# pca9554d-3.net
KiCad netlist of a schematic drawn in EAGLE
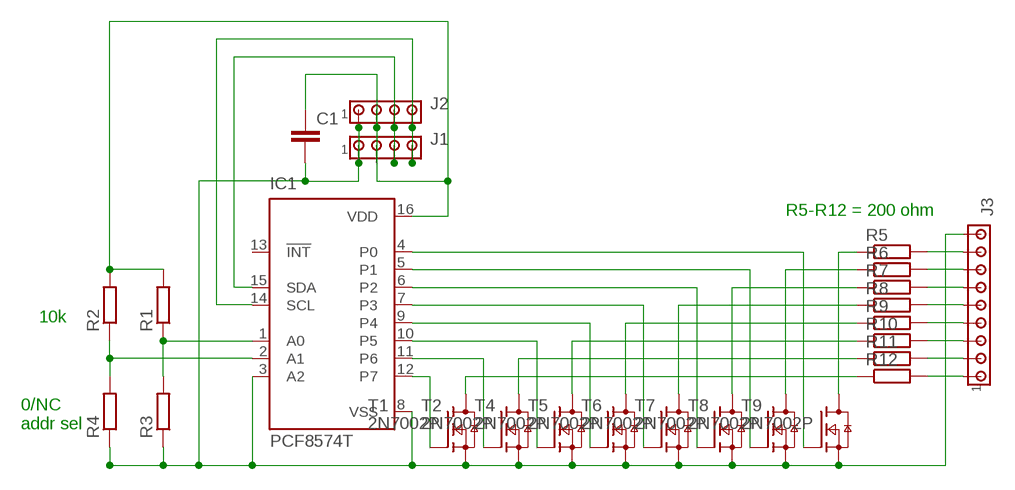
[diagram p0: schematic, sheet 1]

(export (version "E")
  (design (tool "Eeschema 10.0.6"))
  (components
    (comp (ref "C1")
      (value "C-EUC1206")
      (footprint "eagle-import:C1206")
      (libsource (lib "eagle-import") (part "C-EUC1206"))
    )
    (comp (ref "IC1")
      (value "PCF8574T")
      (footprint "eagle-import:SO16W")
      (fields (field (name "MPN") "PCF8574T/3,512"))
      (libsource (lib "eagle-import") (part "PCF8574T"))
    )
    (comp (ref "J1")
      (value "MTA04-100")
      (footprint "eagle-import:10X04MTA")
      (libsource (lib "eagle-import") (part "MTA04-100"))
    )
    (comp (ref "J2")
      (value "MTA04-100")
      (footprint "eagle-import:10X04MTA")
      (libsource (lib "eagle-import") (part "MTA04-100"))
    )
    (comp (ref "J3")
      (value "MTA09-100")
      (footprint "eagle-import:10X09MTA")
      (libsource (lib "eagle-import") (part "MTA09-100"))
    )
    (comp (ref "R1")
      (value "R-EU_R0805")
      (footprint "eagle-import:R0805")
      (libsource (lib "eagle-import") (part "resistor_R-EU_R0805"))
    )
    (comp (ref "R2")
      (value "R-EU_R0805")
      (footprint "eagle-import:R0805")
      (libsource (lib "eagle-import") (part "resistor_R-EU_R0805"))
    )
    (comp (ref "R3")
      (value "R-EU_R0402")
      (footprint "eagle-import:R0402")
      (libsource (lib "eagle-import") (part "R-EU_R0402"))
    )
    (comp (ref "R4")
      (value "R-EU_R0402")
      (footprint "eagle-import:R0402")
      (libsource (lib "eagle-import") (part "R-EU_R0402"))
    )
    (comp (ref "R5")
      (value "R-EU_R0805W")
      (footprint "eagle-import:R0805W")
      (libsource (lib "eagle-import") (part "resistor_R-EU_R0805W"))
    )
    (comp (ref "R6")
      (value "R-EU_R0805W")
      (footprint "eagle-import:R0805W")
      (libsource (lib "eagle-import") (part "resistor_R-EU_R0805W"))
    )
    (comp (ref "R7")
      (value "R-EU_R0805W")
      (footprint "eagle-import:R0805W")
      (libsource (lib "eagle-import") (part "resistor_R-EU_R0805W"))
    )
    (comp (ref "R8")
      (value "R-EU_R0805W")
      (footprint "eagle-import:R0805W")
      (libsource (lib "eagle-import") (part "resistor_R-EU_R0805W"))
    )
    (comp (ref "R9")
      (value "R-EU_R0805W")
      (footprint "eagle-import:R0805W")
      (libsource (lib "eagle-import") (part "resistor_R-EU_R0805W"))
    )
    (comp (ref "R10")
      (value "R-EU_R0805W")
      (footprint "eagle-import:R0805W")
      (libsource (lib "eagle-import") (part "resistor_R-EU_R0805W"))
    )
    (comp (ref "R11")
      (value "R-EU_R0805W")
      (footprint "eagle-import:R0805W")
      (libsource (lib "eagle-import") (part "resistor_R-EU_R0805W"))
    )
    (comp (ref "R12")
      (value "R-EU_R0805W")
      (footprint "eagle-import:R0805W")
      (libsource (lib "eagle-import") (part "resistor_R-EU_R0805W"))
    )
    (comp (ref "T1")
      (value "2N7002P")
      (footprint "eagle-import:SOT23")
      (libsource (lib "eagle-import") (part "2N7002P"))
    )
    (comp (ref "T2")
      (value "2N7002P")
      (footprint "eagle-import:SOT23")
      (libsource (lib "eagle-import") (part "2N7002P"))
    )
    (comp (ref "T4")
      (value "2N7002P")
      (footprint "eagle-import:SOT23")
      (libsource (lib "eagle-import") (part "2N7002P"))
    )
    (comp (ref "T5")
      (value "2N7002P")
      (footprint "eagle-import:SOT23")
      (libsource (lib "eagle-import") (part "2N7002P"))
    )
    (comp (ref "T6")
      (value "2N7002P")
      (footprint "eagle-import:SOT23")
      (libsource (lib "eagle-import") (part "2N7002P"))
    )
    (comp (ref "T7")
      (value "2N7002P")
      (footprint "eagle-import:SOT23")
      (libsource (lib "eagle-import") (part "2N7002P"))
    )
    (comp (ref "T8")
      (value "2N7002P")
      (footprint "eagle-import:SOT23")
      (libsource (lib "eagle-import") (part "2N7002P"))
    )
    (comp (ref "T9")
      (value "2N7002P")
      (footprint "eagle-import:SOT23")
      (libsource (lib "eagle-import") (part "2N7002P"))
    )
  )
  (nets
    (net (code "1") (name "Net-(IC1-A0)") (class "Default")
      (node (ref "IC1") (pin "1") (pinfunction "A0_1") (pintype "input"))
      (node (ref "R1") (pin "1") (pinfunction "1_1") (pintype "passive"))
      (node (ref "R3") (pin "2") (pinfunction "2_2") (pintype "passive"))
    )
    (net (code "2") (name "Net-(IC1-A1)") (class "Default")
      (node (ref "IC1") (pin "2") (pinfunction "A1_2") (pintype "input"))
      (node (ref "R2") (pin "1") (pinfunction "1_1") (pintype "passive"))
      (node (ref "R4") (pin "2") (pinfunction "2_2") (pintype "passive"))
    )
    (net (code "3") (name "Net-(IC1-A2)") (class "Default")
      (node (ref "C1") (pin "2") (pinfunction "2_2") (pintype "passive"))
      (node (ref "IC1") (pin "3") (pinfunction "A2_3") (pintype "input"))
      (node (ref "IC1") (pin "8") (pinfunction "VSS_8") (pintype "power_in"))
      (node (ref "J1") (pin "1") (pinfunction "1_1") (pintype "passive"))
      (node (ref "J2") (pin "1") (pinfunction "1_1") (pintype "passive"))
      (node (ref "J3") (pin "9") (pinfunction "9_9") (pintype "passive"))
      (node (ref "R3") (pin "1") (pinfunction "1_1") (pintype "passive"))
      (node (ref "R4") (pin "1") (pinfunction "1_1") (pintype "passive"))
      (node (ref "T1") (pin "2") (pinfunction "S_2") (pintype "passive"))
      (node (ref "T2") (pin "2") (pinfunction "S_2") (pintype "passive"))
      (node (ref "T4") (pin "2") (pinfunction "S_2") (pintype "passive"))
      (node (ref "T5") (pin "2") (pinfunction "S_2") (pintype "passive"))
      (node (ref "T6") (pin "2") (pinfunction "S_2") (pintype "passive"))
      (node (ref "T7") (pin "2") (pinfunction "S_2") (pintype "passive"))
      (node (ref "T8") (pin "2") (pinfunction "S_2") (pintype "passive"))
      (node (ref "T9") (pin "2") (pinfunction "S_2") (pintype "passive"))
    )
    (net (code "4") (name "Net-(IC1-P0)") (class "Default")
      (node (ref "IC1") (pin "4") (pinfunction "P0_4") (pintype "bidirectional"))
      (node (ref "T9") (pin "1") (pinfunction "G_1") (pintype "passive"))
    )
    (net (code "5") (name "Net-(IC1-P1)") (class "Default")
      (node (ref "IC1") (pin "5") (pinfunction "P1_5") (pintype "bidirectional"))
      (node (ref "T8") (pin "1") (pinfunction "G_1") (pintype "passive"))
    )
    (net (code "6") (name "Net-(IC1-P2)") (class "Default")
      (node (ref "IC1") (pin "6") (pinfunction "P2_6") (pintype "bidirectional"))
      (node (ref "T7") (pin "1") (pinfunction "G_1") (pintype "passive"))
    )
    (net (code "7") (name "Net-(IC1-P3)") (class "Default")
      (node (ref "IC1") (pin "7") (pinfunction "P3_7") (pintype "bidirectional"))
      (node (ref "T6") (pin "1") (pinfunction "G_1") (pintype "passive"))
    )
    (net (code "8") (name "Net-(IC1-P4)") (class "Default")
      (node (ref "IC1") (pin "9") (pinfunction "P4_9") (pintype "bidirectional"))
      (node (ref "T5") (pin "1") (pinfunction "G_1") (pintype "passive"))
    )
    (net (code "9") (name "Net-(IC1-P5)") (class "Default")
      (node (ref "IC1") (pin "10") (pinfunction "P5_10") (pintype "bidirectional"))
      (node (ref "T4") (pin "1") (pinfunction "G_1") (pintype "passive"))
    )
    (net (code "10") (name "Net-(IC1-P6)") (class "Default")
      (node (ref "IC1") (pin "11") (pinfunction "P6_11") (pintype "bidirectional"))
      (node (ref "T2") (pin "1") (pinfunction "G_1") (pintype "passive"))
    )
    (net (code "11") (name "Net-(IC1-P7)") (class "Default")
      (node (ref "IC1") (pin "12") (pinfunction "P7_12") (pintype "bidirectional"))
      (node (ref "T1") (pin "1") (pinfunction "G_1") (pintype "passive"))
    )
    (net (code "12") (name "Net-(IC1-SCL)") (class "Default")
      (node (ref "IC1") (pin "14") (pinfunction "SCL_14") (pintype "input"))
      (node (ref "J1") (pin "4") (pinfunction "4_4") (pintype "passive"))
      (node (ref "J2") (pin "4") (pinfunction "4_4") (pintype "passive"))
    )
    (net (code "13") (name "Net-(IC1-SDA)") (class "Default")
      (node (ref "IC1") (pin "15") (pinfunction "SDA_15") (pintype "bidirectional"))
      (node (ref "J1") (pin "3") (pinfunction "3_3") (pintype "passive"))
      (node (ref "J2") (pin "3") (pinfunction "3_3") (pintype "passive"))
    )
    (net (code "14") (name "Net-(IC1-VDD)") (class "Default")
      (node (ref "C1") (pin "1") (pinfunction "1_1") (pintype "passive"))
      (node (ref "IC1") (pin "16") (pinfunction "VDD_16") (pintype "power_in"))
      (node (ref "J1") (pin "2") (pinfunction "2_2") (pintype "passive"))
      (node (ref "J2") (pin "2") (pinfunction "2_2") (pintype "passive"))
      (node (ref "R1") (pin "2") (pinfunction "2_2") (pintype "passive"))
      (node (ref "R2") (pin "2") (pinfunction "2_2") (pintype "passive"))
    )
    (net (code "15") (name "Net-(J3-Pad1)") (class "Default")
      (node (ref "J3") (pin "1") (pinfunction "1_1") (pintype "passive"))
      (node (ref "R12") (pin "2") (pinfunction "2_2") (pintype "passive"))
    )
    (net (code "16") (name "Net-(J3-Pad2)") (class "Default")
      (node (ref "J3") (pin "2") (pinfunction "2_2") (pintype "passive"))
      (node (ref "R11") (pin "2") (pinfunction "2_2") (pintype "passive"))
    )
    (net (code "17") (name "Net-(J3-Pad3)") (class "Default")
      (node (ref "J3") (pin "3") (pinfunction "3_3") (pintype "passive"))
      (node (ref "R10") (pin "2") (pinfunction "2_2") (pintype "passive"))
    )
    (net (code "18") (name "Net-(J3-Pad4)") (class "Default")
      (node (ref "J3") (pin "4") (pinfunction "4_4") (pintype "passive"))
      (node (ref "R9") (pin "2") (pinfunction "2_2") (pintype "passive"))
    )
    (net (code "19") (name "Net-(J3-Pad5)") (class "Default")
      (node (ref "J3") (pin "5") (pinfunction "5_5") (pintype "passive"))
      (node (ref "R8") (pin "2") (pinfunction "2_2") (pintype "passive"))
    )
    (net (code "20") (name "Net-(J3-Pad6)") (class "Default")
      (node (ref "J3") (pin "6") (pinfunction "6_6") (pintype "passive"))
      (node (ref "R7") (pin "2") (pinfunction "2_2") (pintype "passive"))
    )
    (net (code "21") (name "Net-(J3-Pad7)") (class "Default")
      (node (ref "J3") (pin "7") (pinfunction "7_7") (pintype "passive"))
      (node (ref "R6") (pin "2") (pinfunction "2_2") (pintype "passive"))
    )
    (net (code "22") (name "Net-(J3-Pad8)") (class "Default")
      (node (ref "J3") (pin "8") (pinfunction "8_8") (pintype "passive"))
      (node (ref "R5") (pin "2") (pinfunction "2_2") (pintype "passive"))
    )
    (net (code "23") (name "Net-(T1-D)") (class "Default")
      (node (ref "R12") (pin "1") (pinfunction "1_1") (pintype "passive"))
      (node (ref "T1") (pin "3") (pinfunction "D_3") (pintype "passive"))
    )
    (net (code "24") (name "Net-(T2-D)") (class "Default")
      (node (ref "R11") (pin "1") (pinfunction "1_1") (pintype "passive"))
      (node (ref "T2") (pin "3") (pinfunction "D_3") (pintype "passive"))
    )
    (net (code "25") (name "Net-(T4-D)") (class "Default")
      (node (ref "R10") (pin "1") (pinfunction "1_1") (pintype "passive"))
      (node (ref "T4") (pin "3") (pinfunction "D_3") (pintype "passive"))
    )
    (net (code "26") (name "Net-(T5-D)") (class "Default")
      (node (ref "R9") (pin "1") (pinfunction "1_1") (pintype "passive"))
      (node (ref "T5") (pin "3") (pinfunction "D_3") (pintype "passive"))
    )
    (net (code "27") (name "Net-(T6-D)") (class "Default")
      (node (ref "R8") (pin "1") (pinfunction "1_1") (pintype "passive"))
      (node (ref "T6") (pin "3") (pinfunction "D_3") (pintype "passive"))
    )
    (net (code "28") (name "Net-(T7-D)") (class "Default")
      (node (ref "R7") (pin "1") (pinfunction "1_1") (pintype "passive"))
      (node (ref "T7") (pin "3") (pinfunction "D_3") (pintype "passive"))
    )
    (net (code "29") (name "Net-(T8-D)") (class "Default")
      (node (ref "R6") (pin "1") (pinfunction "1_1") (pintype "passive"))
      (node (ref "T8") (pin "3") (pinfunction "D_3") (pintype "passive"))
    )
    (net (code "30") (name "Net-(T9-D)") (class "Default")
      (node (ref "R5") (pin "1") (pinfunction "1_1") (pintype "passive"))
      (node (ref "T9") (pin "3") (pinfunction "D_3") (pintype "passive"))
    )
    (net (code "31") (name "unconnected-(IC1-~{INT}-Pad13)") (class "Default")
      (node (ref "IC1") (pin "13") (pinfunction "~{INT}_13") (pintype "output"))
    )
  )
)
